# power_REG104GA_1V8.net
KiCad netlist of a schematic drawn in Altium Designer
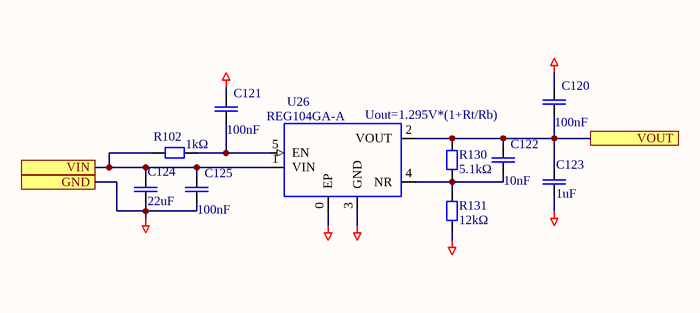
[diagram p0: power_REG104GA_1V8.SchDoc]

(export (version "E")
  (design (tool "Eeschema 10.0.6"))
  (components
    (comp (ref "C120")
      (value "100nF")
      (footprint "CAPC1608N")
      (description "Generic ceramic SMD capacitor")
      (fields (field (name "MAINTAINER") "Evgeniy Kotov"))
      (libsource (lib "[Capacitors] Capacitors SMD") (part "CAPC"))
    )
    (comp (ref "C121")
      (value "100nF")
      (footprint "CAPC1608N")
      (description "Generic ceramic SMD capacitor")
      (fields (field (name "MAINTAINER") "Evgeniy Kotov"))
      (libsource (lib "[Capacitors] Capacitors SMD") (part "CAPC"))
    )
    (comp (ref "C122")
      (value "10nF")
      (footprint "CAPC1608N")
      (description "Generic ceramic SMD capacitor")
      (fields (field (name "MAINTAINER") "Evgeniy Kotov"))
      (libsource (lib "[Capacitors] Capacitors SMD") (part "CAPC"))
    )
    (comp (ref "C123")
      (value "1uF")
      (footprint "CAPC2012N")
      (description "Generic ceramic SMD capacitor")
      (fields (field (name "MAINTAINER") "Evgeniy Kotov"))
      (libsource (lib "[Capacitors] Capacitors SMD") (part "CAPC"))
    )
    (comp (ref "C124")
      (value "22uF")
      (footprint "CAPC2012N")
      (description "Generic ceramic SMD capacitor")
      (fields (field (name "MAINTAINER") "Evgeniy Kotov"))
      (libsource (lib "[Capacitors] Capacitors SMD") (part "CAPC"))
    )
    (comp (ref "C125")
      (value "100nF")
      (footprint "CAPC1608N")
      (description "Generic ceramic SMD capacitor")
      (fields (field (name "MAINTAINER") "Evgeniy Kotov"))
      (libsource (lib "[Capacitors] Capacitors SMD") (part "CAPC"))
    )
    (comp (ref "R102")
      (value "1kΩ")
      (footprint "RESC2012N")
      (description "Resistor, Generic, SMD")
      (fields (field (name "MAINTAINER") "Evgeniy Kotov"))
      (libsource (lib "carrier") (part "RESC"))
    )
    (comp (ref "R130")
      (value "5.1kΩ")
      (footprint "RESC2012N")
      (description "Resistor, Generic, SMD")
      (fields (field (name "MAINTAINER") "Evgeniy Kotov"))
      (libsource (lib "[Resistors] Resistors SMD") (part "RESC"))
    )
    (comp (ref "R131")
      (value "12kΩ")
      (footprint "RESC2012N")
      (description "Resistor, Generic, SMD")
      (fields (field (name "MAINTAINER") "Evgeniy Kotov"))
      (libsource (lib "[Resistors] Resistors SMD") (part "RESC"))
    )
    (comp (ref "U26")
      (value "REG104GA-A")
      (footprint "SOT223")
      (description "Single Output LDO, 1.0A, Adj.(1.295 to 5.5V), Low Noise, Fast Transient Response")
      (fields
        (field (name "MANUFACTURER") "Texas Instruments")
        (field (name "MANUFACTURER_PART_NUMBER") "reg104-a_dcq_6")
      )
      (libsource (lib "Analog & Interface") (part "REG104GA-A"))
    )
  )
  (nets
    (net (code "1") (name "/VIN") (class "Default")
      (node (ref "C124") (pin "2") (pintype "passive"))
      (node (ref "C125") (pin "2") (pintype "passive"))
      (node (ref "R102") (pin "2") (pintype "passive"))
      (node (ref "U26") (pin "1") (pinfunction "VIN_1") (pintype "power_in"))
    )
    (net (code "2") (name "/VOUT") (class "Default")
      (node (ref "C120") (pin "1") (pintype "passive"))
      (node (ref "C122") (pin "2") (pintype "passive"))
      (node (ref "C123") (pin "2") (pintype "passive"))
      (node (ref "R130") (pin "2") (pintype "passive"))
      (node (ref "U26") (pin "2") (pinfunction "VOUT_2") (pintype "power_in"))
    )
    (net (code "3") (name "GND") (class "Default")
      (node (ref "C120") (pin "2") (pintype "passive"))
      (node (ref "C121") (pin "2") (pintype "passive"))
      (node (ref "C123") (pin "1") (pintype "passive"))
      (node (ref "C124") (pin "1") (pintype "passive"))
      (node (ref "C125") (pin "1") (pintype "passive"))
      (node (ref "R131") (pin "1") (pintype "passive"))
      (node (ref "U26") (pin "0") (pinfunction "EP_0") (pintype "passive"))
      (node (ref "U26") (pin "3") (pinfunction "GND_3") (pintype "power_in"))
    )
    (net (code "4") (name "Net-(U26-EN)") (class "Default")
      (node (ref "C121") (pin "1") (pintype "passive"))
      (node (ref "R102") (pin "1") (pintype "passive"))
      (node (ref "U26") (pin "5") (pinfunction "EN_5") (pintype "input"))
    )
    (net (code "5") (name "Net-(U26-NR)") (class "Default")
      (node (ref "C122") (pin "1") (pintype "passive"))
      (node (ref "R130") (pin "1") (pintype "passive"))
      (node (ref "R131") (pin "2") (pintype "passive"))
      (node (ref "U26") (pin "4") (pinfunction "NR_4") (pintype "passive"))
    )
  )
)
